# HshMain_v1_1.net
KiCad netlist of a schematic drawn in EAGLE
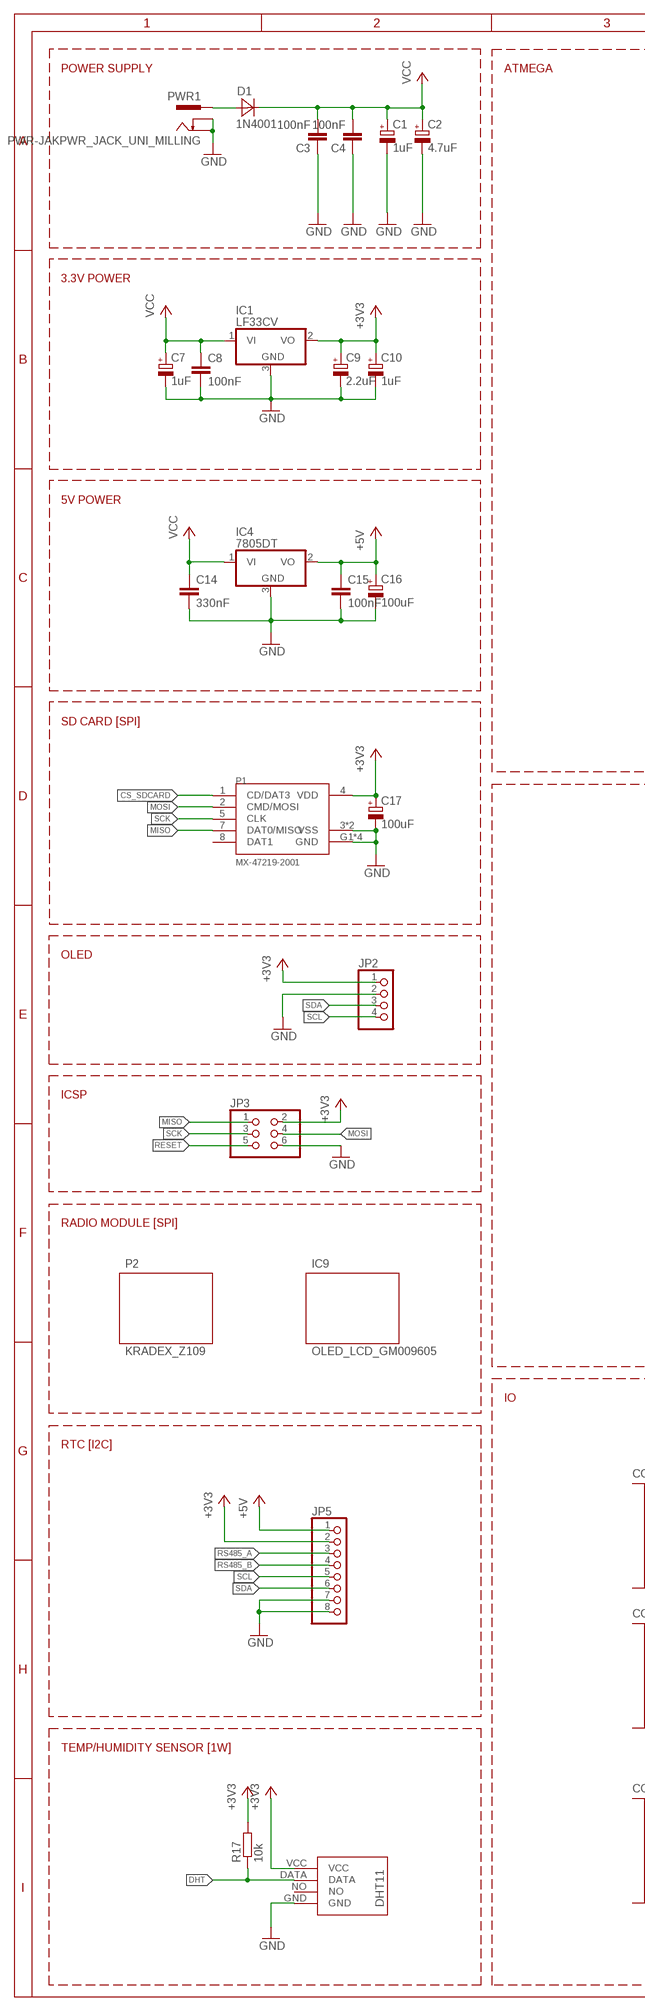
[diagram p0: schematic, sheet 1, part 1 of 2]
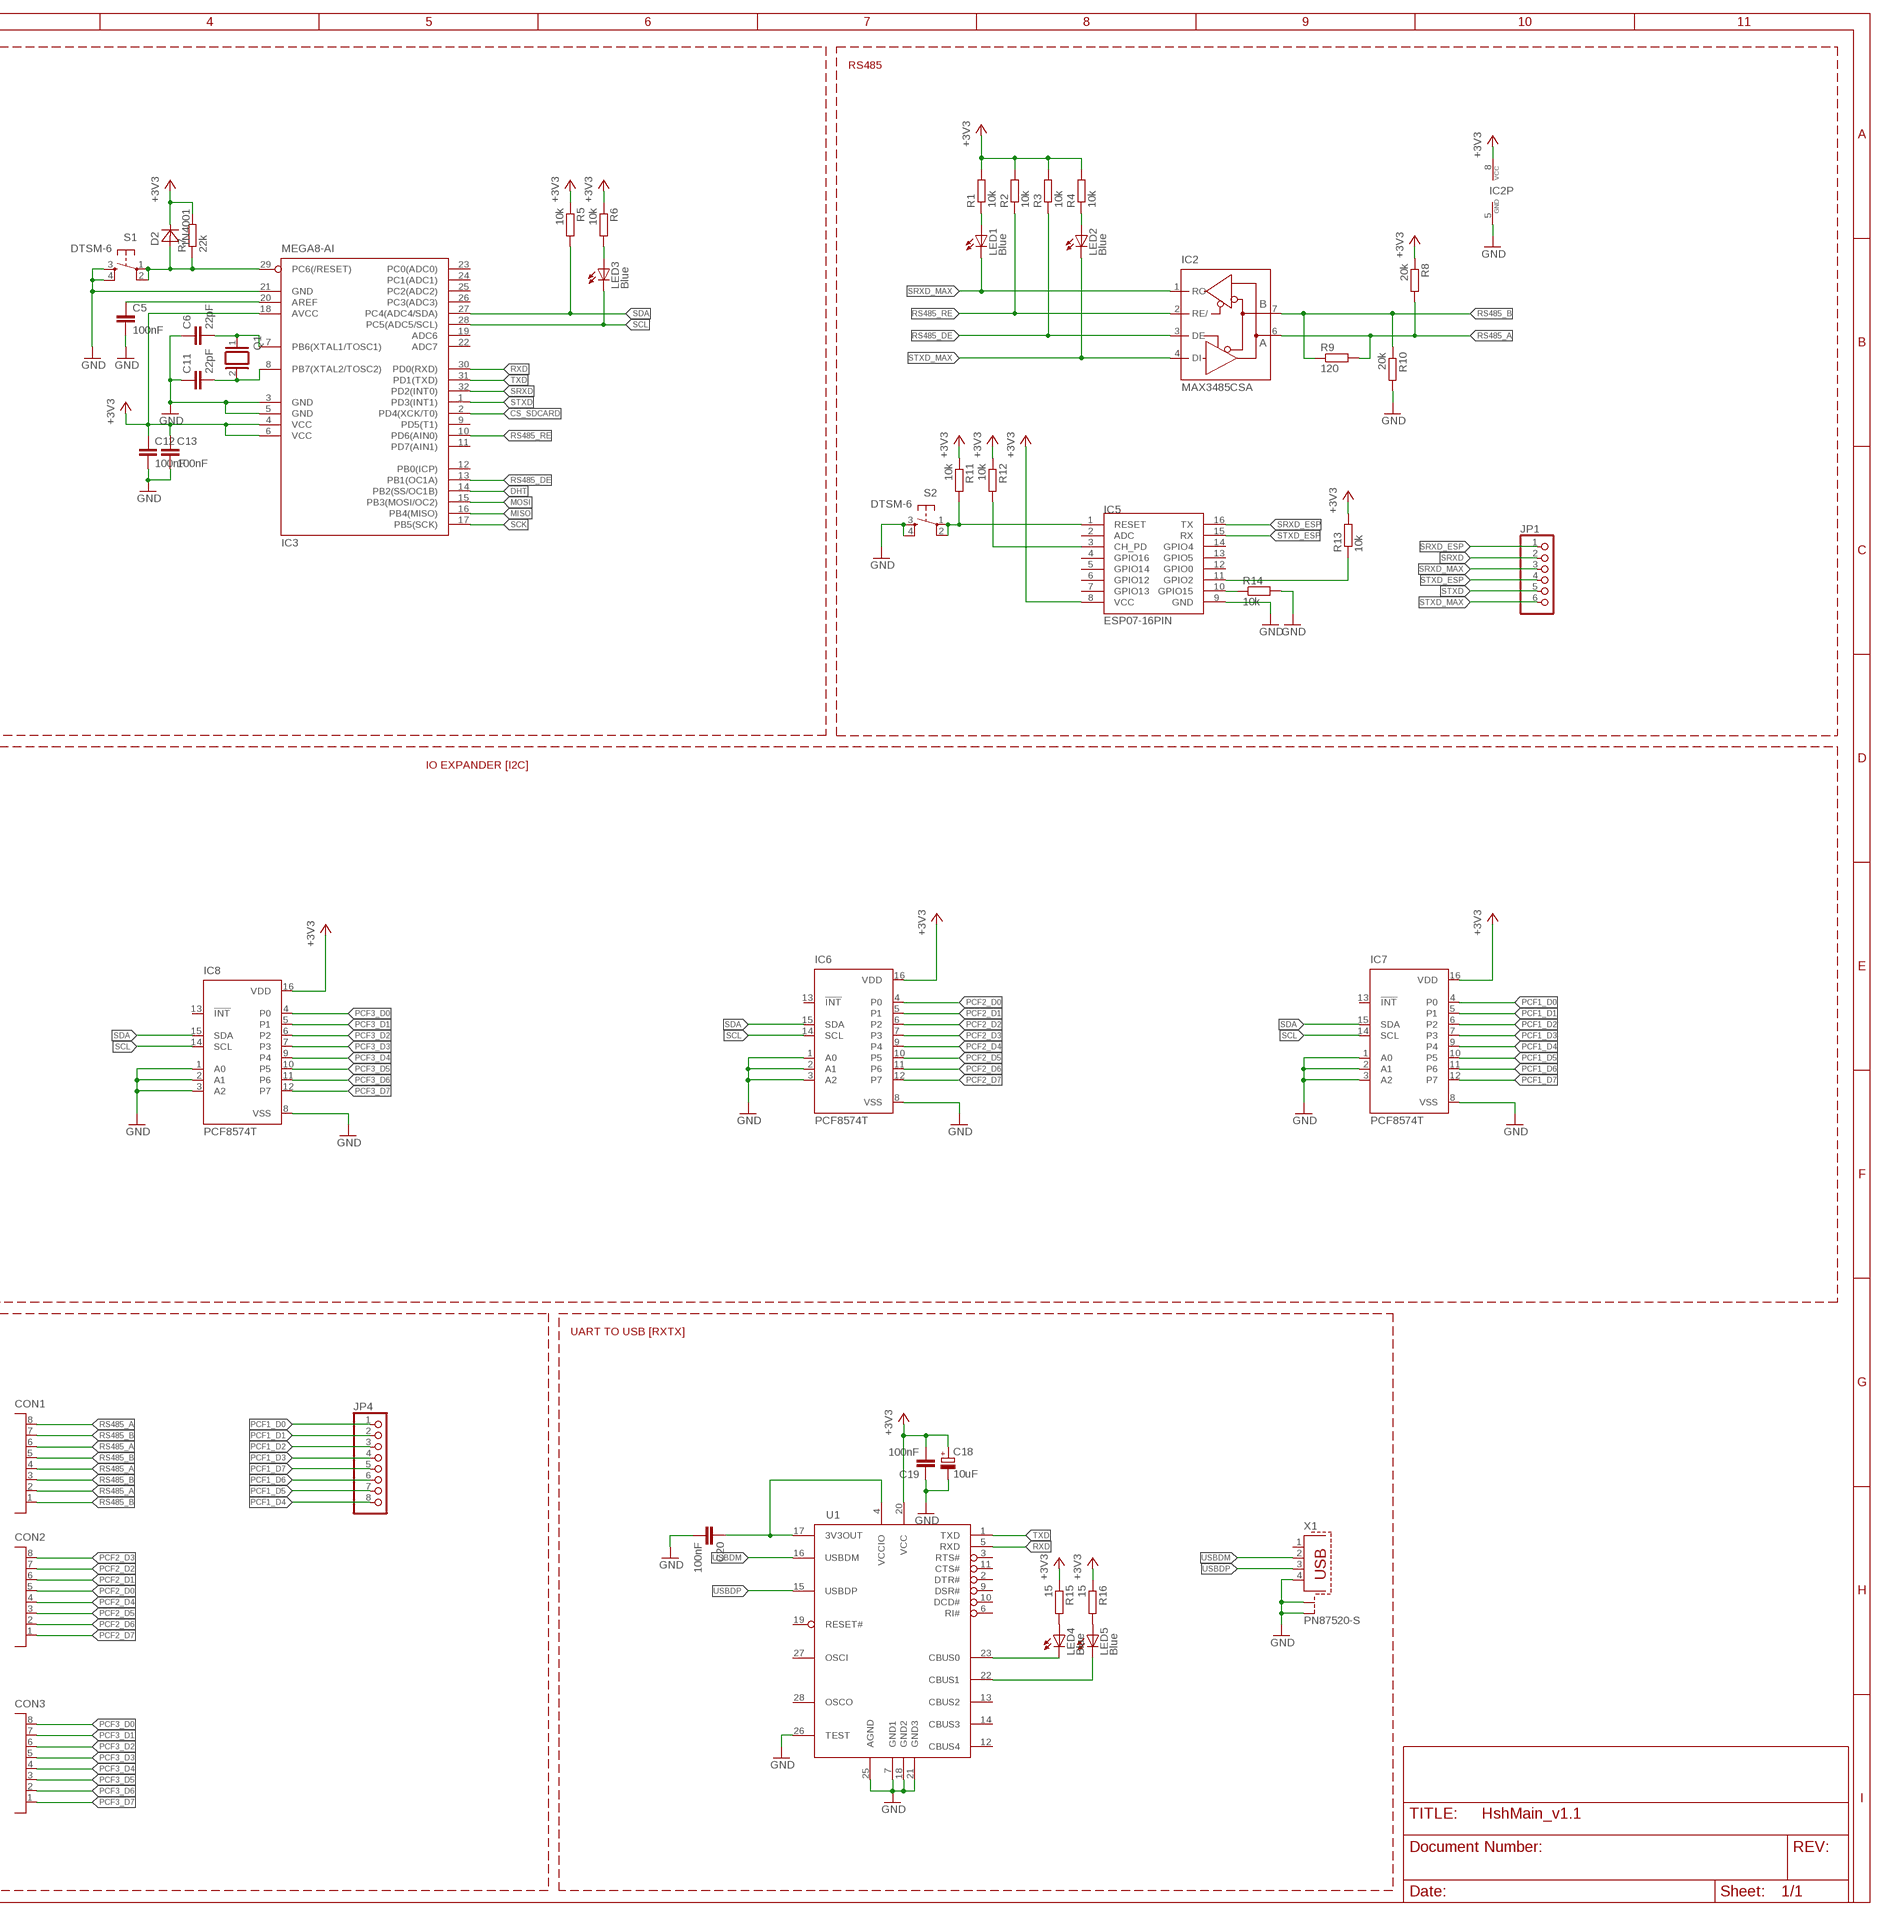
[diagram p1: schematic, sheet 1, part 2 of 2]

(export (version "E")
  (design (tool "Eeschema 10.0.6"))
  (components
    (comp (ref "C1")
      (value "1uF")
      (footprint "eagle-import:PANASONIC_B")
      (libsource (lib "eagle-import") (part "CPOL-EUB"))
    )
    (comp (ref "C2")
      (value "4.7uF")
      (footprint "eagle-import:PANASONIC_B")
      (libsource (lib "eagle-import") (part "CPOL-EUB"))
    )
    (comp (ref "C3")
      (value "100nF")
      (footprint "eagle-import:C0805")
      (libsource (lib "eagle-import") (part "C-EUC0805"))
    )
    (comp (ref "C4")
      (value "100nF")
      (footprint "eagle-import:C0805")
      (libsource (lib "eagle-import") (part "C-EUC0805"))
    )
    (comp (ref "C5")
      (value "100nF")
      (footprint "eagle-import:C0805")
      (libsource (lib "eagle-import") (part "C-EUC0805"))
    )
    (comp (ref "C6")
      (value "22pF")
      (footprint "eagle-import:C0805")
      (libsource (lib "eagle-import") (part "C-EUC0805"))
    )
    (comp (ref "C7")
      (value "1uF")
      (footprint "eagle-import:PANASONIC_B")
      (libsource (lib "eagle-import") (part "CPOL-EUB"))
    )
    (comp (ref "C8")
      (value "100nF")
      (footprint "eagle-import:C0805")
      (libsource (lib "eagle-import") (part "C-EUC0805"))
    )
    (comp (ref "C9")
      (value "2.2uF")
      (footprint "eagle-import:PANASONIC_B")
      (libsource (lib "eagle-import") (part "CPOL-EUB"))
    )
    (comp (ref "C10")
      (value "1uF")
      (footprint "eagle-import:PANASONIC_B")
      (libsource (lib "eagle-import") (part "CPOL-EUB"))
    )
    (comp (ref "C11")
      (value "22pF")
      (footprint "eagle-import:C0805")
      (libsource (lib "eagle-import") (part "C-EUC0805"))
    )
    (comp (ref "C12")
      (value "100nF")
      (footprint "eagle-import:C0805")
      (libsource (lib "eagle-import") (part "C-EUC0805"))
    )
    (comp (ref "C13")
      (value "100nF")
      (footprint "eagle-import:C0805")
      (libsource (lib "eagle-import") (part "C-EUC0805"))
    )
    (comp (ref "C14")
      (value "330nF")
      (footprint "eagle-import:C0805")
      (libsource (lib "eagle-import") (part "C-EUC0805"))
    )
    (comp (ref "C15")
      (value "100nF")
      (footprint "eagle-import:C0805")
      (libsource (lib "eagle-import") (part "C-EUC0805"))
    )
    (comp (ref "C16")
      (value "100uF")
      (footprint "eagle-import:PANASONIC_D")
      (libsource (lib "eagle-import") (part "CPOL-EUD"))
    )
    (comp (ref "C17")
      (value "100uF")
      (footprint "eagle-import:PANASONIC_D")
      (libsource (lib "eagle-import") (part "CPOL-EUD"))
    )
    (comp (ref "C18")
      (value "10uF")
      (footprint "eagle-import:PANASONIC_B")
      (libsource (lib "eagle-import") (part "CPOL-EUB"))
    )
    (comp (ref "C19")
      (value "100nF")
      (footprint "eagle-import:C0805")
      (libsource (lib "eagle-import") (part "C-EUC0805"))
    )
    (comp (ref "C20")
      (value "100nF")
      (footprint "eagle-import:C0805")
      (libsource (lib "eagle-import") (part "C-EUC0805"))
    )
    (comp (ref "CON1")
      (value "15EDGRC-3.81-8P")
      (footprint "eagle-import:15EDGRC-3.81-8P")
      (libsource (lib "eagle-import") (part "15EDGRC-3.81-8P"))
    )
    (comp (ref "CON2")
      (value "15EDGRC-3.81-8P")
      (footprint "eagle-import:15EDGRC-3.81-8P")
      (libsource (lib "eagle-import") (part "15EDGRC-3.81-8P"))
    )
    (comp (ref "CON3")
      (value "15EDGRC-3.81-8P")
      (footprint "eagle-import:15EDGRC-3.81-8P")
      (libsource (lib "eagle-import") (part "15EDGRC-3.81-8P"))
    )
    (comp (ref "D1")
      (value "1N4001")
      (footprint "eagle-import:SMA")
      (libsource (lib "eagle-import") (part "MBRA340T3"))
    )
    (comp (ref "D2")
      (value "1N4001")
      (footprint "eagle-import:SMA")
      (libsource (lib "eagle-import") (part "MBRA340T3"))
    )
    (comp (ref "IC1")
      (value "LF33CV")
      (footprint "eagle-import:TO252")
      (libsource (lib "eagle-import") (part "78DT"))
    )
    (comp (ref "IC2")
      (value "MAX3485CSA")
      (footprint "eagle-import:SO08")
      (fields (field (name "MF") "MAXIM") (field (name "MPN") "MAX481CSA"))
      (libsource (lib "eagle-import") (part "MAX481CSA"))
    )
    (comp (ref "IC3")
      (value "MEGA8-AI")
      (footprint "eagle-import:TQFP32-08")
      (fields (field (name "MPN") "ATMEGA8-16AU"))
      (libsource (lib "eagle-import") (part "MEGA8-AI"))
    )
    (comp (ref "IC4")
      (value "7805DT")
      (footprint "eagle-import:TO252")
      (libsource (lib "eagle-import") (part "linear_78DT05"))
    )
    (comp (ref "IC5")
      (value "ESP07-16PIN")
      (footprint "eagle-import:ESP07-16PIN")
      (libsource (lib "eagle-import") (part "ESP07-16PIN"))
    )
    (comp (ref "IC6")
      (value "PCF8574T")
      (footprint "eagle-import:SO16W")
      (fields (field (name "MPN") "PCF8574T/3,512"))
      (libsource (lib "eagle-import") (part "PCF8574T"))
    )
    (comp (ref "IC7")
      (value "PCF8574T")
      (footprint "eagle-import:SO16W")
      (fields (field (name "MPN") "PCF8574T/3,512"))
      (libsource (lib "eagle-import") (part "PCF8574T"))
    )
    (comp (ref "IC8")
      (value "PCF8574T")
      (footprint "eagle-import:SO16W")
      (fields (field (name "MPN") "PCF8574T/3,512"))
      (libsource (lib "eagle-import") (part "PCF8574T"))
    )
    (comp (ref "IC9")
      (value "OLED_LCD_GM009605")
      (footprint "eagle-import:OLED_LCD_GM009605")
      (libsource (lib "eagle-import") (part "OLED_LCD_GM009605"))
    )
    (comp (ref "IC10")
      (value "DHT11-PION.")
      (footprint "eagle-import:DHT11-PION.")
      (libsource (lib "eagle-import") (part "DHT11-PION."))
    )
    (comp (ref "JP1")
      (value "PINHD-1X6")
      (footprint "eagle-import:1X06")
      (libsource (lib "eagle-import") (part "PINHD-1X6"))
    )
    (comp (ref "JP2")
      (value "PINHD-1X4")
      (footprint "eagle-import:1X04")
      (libsource (lib "eagle-import") (part "PINHD-1X4"))
    )
    (comp (ref "JP3")
      (value "PINHD-2X3")
      (footprint "eagle-import:2X03")
      (libsource (lib "eagle-import") (part "PINHD-2X3"))
    )
    (comp (ref "JP4")
      (value "PINHD-1X8")
      (footprint "eagle-import:1X08")
      (libsource (lib "eagle-import") (part "PINHD-1X8"))
    )
    (comp (ref "JP5")
      (value "PINHD-1X8/90")
      (footprint "eagle-import:1X08_90")
      (libsource (lib "eagle-import") (part "PINHD-1X8/90"))
    )
    (comp (ref "LED1")
      (value "Blue")
      (footprint "eagle-import:SML0805")
      (libsource (lib "eagle-import") (part "LEDSML0805"))
    )
    (comp (ref "LED2")
      (value "Blue")
      (footprint "eagle-import:SML0805")
      (libsource (lib "eagle-import") (part "LEDSML0805"))
    )
    (comp (ref "LED3")
      (value "Blue")
      (footprint "eagle-import:SML0805")
      (libsource (lib "eagle-import") (part "LEDSML0805"))
    )
    (comp (ref "LED4")
      (value "Blue")
      (footprint "eagle-import:SML0805")
      (libsource (lib "eagle-import") (part "LEDSML0805"))
    )
    (comp (ref "LED5")
      (value "Blue")
      (footprint "eagle-import:SML0805")
      (libsource (lib "eagle-import") (part "LEDSML0805"))
    )
    (comp (ref "P1")
      (value "MX-47219-2001")
      (footprint "eagle-import:MX-47219-2001")
      (libsource (lib "eagle-import") (part "MX-47219-2001"))
    )
    (comp (ref "P2")
      (value "KRADEX_Z109")
      (footprint "eagle-import:KRADEX_Z109")
      (libsource (lib "eagle-import") (part "KRADEX_Z109"))
    )
    (comp (ref "PWR1")
      (value "PWR-JAKPWR_JACK_UNI_MILLING")
      (footprint "eagle-import:PWR_JACK_UNI_MILLING")
      (libsource (lib "eagle-import") (part "PWR-JAKPWR_JACK_UNI_MILLING"))
    )
    (comp (ref "Q1")
      (value "XTAL/S")
      (footprint "eagle-import:QS")
      (libsource (lib "eagle-import") (part "XTAL/S"))
    )
    (comp (ref "R1")
      (value "10k")
      (footprint "eagle-import:R0805")
      (libsource (lib "eagle-import") (part "R-EU_R0805"))
    )
    (comp (ref "R2")
      (value "10k")
      (footprint "eagle-import:R0805")
      (libsource (lib "eagle-import") (part "R-EU_R0805"))
    )
    (comp (ref "R3")
      (value "10k")
      (footprint "eagle-import:R0805")
      (libsource (lib "eagle-import") (part "R-EU_R0805"))
    )
    (comp (ref "R4")
      (value "10k")
      (footprint "eagle-import:R0805")
      (libsource (lib "eagle-import") (part "R-EU_R0805"))
    )
    (comp (ref "R5")
      (value "10k")
      (footprint "eagle-import:R0805")
      (libsource (lib "eagle-import") (part "R-EU_R0805"))
    )
    (comp (ref "R6")
      (value "10k")
      (footprint "eagle-import:R0805")
      (libsource (lib "eagle-import") (part "R-EU_R0805"))
    )
    (comp (ref "R7")
      (value "22k")
      (footprint "eagle-import:R0805")
      (libsource (lib "eagle-import") (part "R-EU_R0805"))
    )
    (comp (ref "R8")
      (value "20k")
      (footprint "eagle-import:R0805")
      (libsource (lib "eagle-import") (part "R-EU_R0805"))
    )
    (comp (ref "R9")
      (value "120")
      (footprint "eagle-import:R0805")
      (libsource (lib "eagle-import") (part "R-EU_R0805"))
    )
    (comp (ref "R10")
      (value "20k")
      (footprint "eagle-import:R0805")
      (libsource (lib "eagle-import") (part "R-EU_R0805"))
    )
    (comp (ref "R11")
      (value "10k")
      (footprint "eagle-import:R0805")
      (libsource (lib "eagle-import") (part "R-EU_R0805"))
    )
    (comp (ref "R12")
      (value "10k")
      (footprint "eagle-import:R0805")
      (libsource (lib "eagle-import") (part "R-EU_R0805"))
    )
    (comp (ref "R13")
      (value "10k")
      (footprint "eagle-import:R0805")
      (libsource (lib "eagle-import") (part "R-EU_R0805"))
    )
    (comp (ref "R14")
      (value "10k")
      (footprint "eagle-import:R0805")
      (libsource (lib "eagle-import") (part "R-EU_R0805"))
    )
    (comp (ref "R15")
      (value "15")
      (footprint "eagle-import:R0805")
      (libsource (lib "eagle-import") (part "R-EU_R0805"))
    )
    (comp (ref "R16")
      (value "15")
      (footprint "eagle-import:R0805")
      (libsource (lib "eagle-import") (part "R-EU_R0805"))
    )
    (comp (ref "R17")
      (value "10k")
      (footprint "eagle-import:R0805")
      (libsource (lib "eagle-import") (part "R-EU_R0805"))
    )
    (comp (ref "S1")
      (value "DTSM-6")
      (footprint "eagle-import:DTSM-6")
      (libsource (lib "eagle-import") (part "DTSM-6"))
    )
    (comp (ref "S2")
      (value "DTSM-6")
      (footprint "eagle-import:DTSM-6")
      (libsource (lib "eagle-import") (part "DTSM-6"))
    )
    (comp (ref "U1")
      (value "FT232RL")
      (footprint "eagle-import:SSOP28DB")
      (libsource (lib "eagle-import") (part "FT232RL"))
    )
    (comp (ref "X1")
      (value "PN87520-S")
      (footprint "eagle-import:PN87520-S")
      (libsource (lib "eagle-import") (part "PN87520-S"))
    )
  )
  (nets
    (net (code "1") (name "+3V3") (class "Default")
      (node (ref "C10") (pin "+") (pinfunction "+_+") (pintype "passive"))
      (node (ref "C12") (pin "1") (pinfunction "1_1") (pintype "passive"))
      (node (ref "C13") (pin "1") (pinfunction "1_1") (pintype "passive"))
      (node (ref "C17") (pin "+") (pinfunction "+_+") (pintype "passive"))
      (node (ref "C18") (pin "+") (pinfunction "+_+") (pintype "passive"))
      (node (ref "C19") (pin "2") (pinfunction "2_2") (pintype "passive"))
      (node (ref "C9") (pin "+") (pinfunction "+_+") (pintype "passive"))
      (node (ref "D2") (pin "C") (pinfunction "C_C") (pintype "passive"))
      (node (ref "IC1") (pin "2") (pinfunction "VO_2") (pintype "passive"))
      (node (ref "IC10") (pin "VCC") (pinfunction "VCC_VCC") (pintype "bidirectional"))
      (node (ref "IC2") (pin "8") (pinfunction "VCC_8") (pintype "power_in"))
      (node (ref "IC3") (pin "18") (pinfunction "AVCC_18") (pintype "power_in"))
      (node (ref "IC3") (pin "4") (pinfunction "VCC_4") (pintype "power_in"))
      (node (ref "IC3") (pin "6") (pinfunction "VCC_6") (pintype "power_in"))
      (node (ref "IC5") (pin "8") (pinfunction "VCC_8") (pintype "bidirectional"))
      (node (ref "IC6") (pin "16") (pinfunction "VDD_16") (pintype "power_in"))
      (node (ref "IC7") (pin "16") (pinfunction "VDD_16") (pintype "power_in"))
      (node (ref "IC8") (pin "16") (pinfunction "VDD_16") (pintype "power_in"))
      (node (ref "JP2") (pin "1") (pinfunction "1_1") (pintype "passive"))
      (node (ref "JP3") (pin "2") (pinfunction "2_2") (pintype "passive"))
      (node (ref "JP5") (pin "2") (pinfunction "2_2") (pintype "passive"))
      (node (ref "P1") (pin "4") (pinfunction "VDD_4") (pintype "bidirectional"))
      (node (ref "R1") (pin "2") (pinfunction "2_2") (pintype "passive"))
      (node (ref "R11") (pin "1") (pinfunction "1_1") (pintype "passive"))
      (node (ref "R12") (pin "1") (pinfunction "1_1") (pintype "passive"))
      (node (ref "R13") (pin "2") (pinfunction "2_2") (pintype "passive"))
      (node (ref "R15") (pin "1") (pinfunction "1_1") (pintype "passive"))
      (node (ref "R16") (pin "1") (pinfunction "1_1") (pintype "passive"))
      (node (ref "R17") (pin "2") (pinfunction "2_2") (pintype "passive"))
      (node (ref "R2") (pin "2") (pinfunction "2_2") (pintype "passive"))
      (node (ref "R3") (pin "2") (pinfunction "2_2") (pintype "passive"))
      (node (ref "R4") (pin "2") (pinfunction "2_2") (pintype "passive"))
      (node (ref "R5") (pin "1") (pinfunction "1_1") (pintype "passive"))
      (node (ref "R6") (pin "1") (pinfunction "1_1") (pintype "passive"))
      (node (ref "R7") (pin "2") (pinfunction "2_2") (pintype "passive"))
      (node (ref "R8") (pin "1") (pinfunction "1_1") (pintype "passive"))
      (node (ref "U1") (pin "20") (pinfunction "VCC_20") (pintype "power_in"))
    )
    (net (code "2") (name "+5V") (class "Default")
      (node (ref "C15") (pin "1") (pinfunction "1_1") (pintype "passive"))
      (node (ref "C16") (pin "+") (pinfunction "+_+") (pintype "passive"))
      (node (ref "IC4") (pin "2") (pinfunction "VO_2") (pintype "passive"))
      (node (ref "JP5") (pin "1") (pinfunction "1_1") (pintype "passive"))
    )
    (net (code "3") (name "CS_SDCARD") (class "Default")
      (node (ref "IC3") (pin "2") (pinfunction "PD4(XCK/T0)_2") (pintype "bidirectional"))
      (node (ref "P1") (pin "1") (pinfunction "CD/DAT3_1") (pintype "bidirectional"))
    )
    (net (code "4") (name "DHT") (class "Default")
      (node (ref "IC10") (pin "DATA") (pinfunction "DATA_DATA") (pintype "bidirectional"))
      (node (ref "IC3") (pin "14") (pinfunction "PB2(SS/OC1B)_14") (pintype "bidirectional"))
      (node (ref "R17") (pin "1") (pinfunction "1_1") (pintype "passive"))
    )
    (net (code "5") (name "GND") (class "Default")
      (node (ref "C1") (pin "-") (pinfunction "-_-") (pintype "passive"))
      (node (ref "C10") (pin "-") (pinfunction "-_-") (pintype "passive"))
      (node (ref "C11") (pin "1") (pinfunction "1_1") (pintype "passive"))
      (node (ref "C12") (pin "2") (pinfunction "2_2") (pintype "passive"))
      (node (ref "C13") (pin "2") (pinfunction "2_2") (pintype "passive"))
      (node (ref "C14") (pin "2") (pinfunction "2_2") (pintype "passive"))
      (node (ref "C15") (pin "2") (pinfunction "2_2") (pintype "passive"))
      (node (ref "C16") (pin "-") (pinfunction "-_-") (pintype "passive"))
      (node (ref "C17") (pin "-") (pinfunction "-_-") (pintype "passive"))
      (node (ref "C18") (pin "-") (pinfunction "-_-") (pintype "passive"))
      (node (ref "C19") (pin "1") (pinfunction "1_1") (pintype "passive"))
      (node (ref "C2") (pin "-") (pinfunction "-_-") (pintype "passive"))
      (node (ref "C20") (pin "2") (pinfunction "2_2") (pintype "passive"))
      (node (ref "C3") (pin "1") (pinfunction "1_1") (pintype "passive"))
      (node (ref "C4") (pin "1") (pinfunction "1_1") (pintype "passive"))
      (node (ref "C5") (pin "2") (pinfunction "2_2") (pintype "passive"))
      (node (ref "C6") (pin "1") (pinfunction "1_1") (pintype "passive"))
      (node (ref "C7") (pin "-") (pinfunction "-_-") (pintype "passive"))
      (node (ref "C8") (pin "2") (pinfunction "2_2") (pintype "passive"))
      (node (ref "C9") (pin "-") (pinfunction "-_-") (pintype "passive"))
      (node (ref "IC1") (pin "3") (pinfunction "GND_3") (pintype "passive"))
      (node (ref "IC10") (pin "GND") (pinfunction "GND_GND") (pintype "bidirectional"))
      (node (ref "IC2") (pin "5") (pinfunction "GND_5") (pintype "power_in"))
      (node (ref "IC3") (pin "21") (pinfunction "GND_21") (pintype "power_in"))
      (node (ref "IC3") (pin "3") (pinfunction "GND_3") (pintype "power_in"))
      (node (ref "IC3") (pin "5") (pinfunction "GND_5") (pintype "power_in"))
      (node (ref "IC4") (pin "3") (pinfunction "GND_3") (pintype "passive"))
      (node (ref "IC5") (pin "9") (pinfunction "GND_9") (pintype "bidirectional"))
      (node (ref "IC6") (pin "1") (pinfunction "A0_1") (pintype "input"))
      (node (ref "IC6") (pin "2") (pinfunction "A1_2") (pintype "input"))
      (node (ref "IC6") (pin "3") (pinfunction "A2_3") (pintype "input"))
      (node (ref "IC6") (pin "8") (pinfunction "VSS_8") (pintype "power_in"))
      (node (ref "IC7") (pin "1") (pinfunction "A0_1") (pintype "input"))
      (node (ref "IC7") (pin "2") (pinfunction "A1_2") (pintype "input"))
      (node (ref "IC7") (pin "3") (pinfunction "A2_3") (pintype "input"))
      (node (ref "IC7") (pin "8") (pinfunction "VSS_8") (pintype "power_in"))
      (node (ref "IC8") (pin "1") (pinfunction "A0_1") (pintype "input"))
      (node (ref "IC8") (pin "2") (pinfunction "A1_2") (pintype "input"))
      (node (ref "IC8") (pin "3") (pinfunction "A2_3") (pintype "input"))
      (node (ref "IC8") (pin "8") (pinfunction "VSS_8") (pintype "power_in"))
      (node (ref "JP2") (pin "2") (pinfunction "2_2") (pintype "passive"))
      (node (ref "JP3") (pin "6") (pinfunction "6_6") (pintype "passive"))
      (node (ref "JP5") (pin "7") (pinfunction "7_7") (pintype "passive"))
      (node (ref "JP5") (pin "8") (pinfunction "8_8") (pintype "passive"))
      (node (ref "P1") (pin "3") (pinfunction "VSS_3") (pintype "bidirectional"))
      (node (ref "P1") (pin "6") (pinfunction "VSS_6") (pintype "bidirectional"))
      (node (ref "P1") (pin "G1") (pinfunction "GND_G1") (pintype "bidirectional"))
      (node (ref "P1") (pin "G2") (pinfunction "GND_G2") (pintype "bidirectional"))
      (node (ref "P1") (pin "G3") (pinfunction "GND_G3") (pintype "bidirectional"))
      (node (ref "P1") (pin "G4") (pinfunction "GND_G4") (pintype "bidirectional"))
      (node (ref "PWR1") (pin "-") (pinfunction "-_-") (pintype "passive"))
      (node (ref "PWR1") (pin "--") (pinfunction "--_--") (pintype "passive"))
      (node (ref "PWR1") (pin "--1") (pinfunction "--_--1") (pintype "passive"))
      (node (ref "PWR1") (pin "--2") (pinfunction "--_--2") (pintype "passive"))
      (node (ref "PWR1") (pin "--3") (pinfunction "--_--3") (pintype "passive"))
      (node (ref "PWR1") (pin "--4") (pinfunction "--_--4") (pintype "passive"))
      (node (ref "PWR1") (pin "--5") (pinfunction "--_--5") (pintype "passive"))
      (node (ref "PWR1") (pin "--6") (pinfunction "--_--6") (pintype "passive"))
      (node (ref "PWR1") (pin "--7") (pinfunction "--_--7") (pintype "passive"))
      (node (ref "PWR1") (pin "--8") (pinfunction "--_--8") (pintype "passive"))
      (node (ref "PWR1") (pin "-1") (pinfunction "-_-1") (pintype "passive"))
      (node (ref "PWR1") (pin "-2") (pinfunction "-_-2") (pintype "passive"))
      (node (ref "PWR1") (pin "-3") (pinfunction "-_-3") (pintype "passive"))
      (node (ref "PWR1") (pin "-4") (pinfunction "-_-4") (pintype "passive"))
      (node (ref "PWR1") (pin "-5") (pinfunction "-_-5") (pintype "passive"))
      (node (ref "PWR1") (pin "-6") (pinfunction "-_-6") (pintype "passive"))
      (node (ref "PWR1") (pin "-7") (pinfunction "-_-7") (pintype "passive"))
      (node (ref "PWR1") (pin "-8") (pinfunction "-_-8") (pintype "passive"))
      (node (ref "R10") (pin "2") (pinfunction "2_2") (pintype "passive"))
      (node (ref "R14") (pin "2") (pinfunction "2_2") (pintype "passive"))
      (node (ref "S1") (pin "3") (pinfunction "3_3") (pintype "passive"))
      (node (ref "S1") (pin "4") (pinfunction "4_4") (pintype "passive"))
      (node (ref "S2") (pin "3") (pinfunction "3_3") (pintype "passive"))
      (node (ref "S2") (pin "4") (pinfunction "4_4") (pintype "passive"))
      (node (ref "U1") (pin "18") (pinfunction "GND2_18") (pintype "power_in"))
      (node (ref "U1") (pin "21") (pinfunction "GND3_21") (pintype "power_in"))
      (node (ref "U1") (pin "25") (pinfunction "AGND_25") (pintype "power_in"))
      (node (ref "U1") (pin "26") (pinfunction "TEST_26") (pintype "input"))
      (node (ref "U1") (pin "7") (pinfunction "GND1_7") (pintype "power_in"))
      (node (ref "X1") (pin "4") (pinfunction "4_4") (pintype "passive"))
      (node (ref "X1") (pin "S1") (pinfunction "S1_S1") (pintype "passive"))
      (node (ref "X1") (pin "S2") (pinfunction "S2_S2") (pintype "passive"))
    )
    (net (code "6") (name "MISO") (class "Default")
      (node (ref "IC3") (pin "16") (pinfunction "PB4(MISO)_16") (pintype "bidirectional"))
      (node (ref "JP3") (pin "1") (pinfunction "1_1") (pintype "passive"))
      (node (ref "P1") (pin "7") (pinfunction "DAT0/MISO_7") (pintype "bidirectional"))
    )
    (net (code "7") (name "MOSI") (class "Default")
      (node (ref "IC3") (pin "15") (pinfunction "PB3(MOSI/OC2)_15") (pintype "bidirectional"))
      (node (ref "JP3") (pin "4") (pinfunction "4_4") (pintype "passive"))
      (node (ref "P1") (pin "2") (pinfunction "CMD/MOSI_2") (pintype "bidirectional"))
    )
    (net (code "8") (name "Net-(D1-PadA)") (class "Default")
      (node (ref "D1") (pin "A") (pinfunction "A_A") (pintype "passive"))
      (node (ref "PWR1") (pin "+") (pinfunction "+_+") (pintype "passive"))
      (node (ref "PWR1") (pin "+1") (pinfunction "+_+1") (pintype "passive"))
      (node (ref "PWR1") (pin "+2") (pinfunction "+_+2") (pintype "passive"))
      (node (ref "PWR1") (pin "+3") (pinfunction "+_+3") (pintype "passive"))
      (node (ref "PWR1") (pin "+4") (pinfunction "+_+4") (pintype "passive"))
      (node (ref "PWR1") (pin "+5") (pinfunction "+_+5") (pintype "passive"))
      (node (ref "PWR1") (pin "+6") (pinfunction "+_+6") (pintype "passive"))
      (node (ref "PWR1") (pin "+7") (pinfunction "+_+7") (pintype "passive"))
      (node (ref "PWR1") (pin "+8") (pinfunction "+_+8") (pintype "passive"))
    )
    (net (code "9") (name "Net-(IC3-AREF)") (class "Default")
      (node (ref "C5") (pin "1") (pinfunction "1_1") (pintype "passive"))
      (node (ref "IC3") (pin "20") (pinfunction "AREF_20") (pintype "passive"))
    )
    (net (code "10") (name "Net-(IC3-PB6(XTAL1{slash}TOSC1))") (class "Default")
      (node (ref "C6") (pin "2") (pinfunction "2_2") (pintype "passive"))
      (node (ref "IC3") (pin "7") (pinfunction "PB6(XTAL1/TOSC1)_7") (pintype "bidirectional"))
      (node (ref "Q1") (pin "1") (pinfunction "1_1") (pintype "passive"))
    )
    (net (code "11") (name "Net-(IC3-PB7(XTAL2{slash}TOSC2))") (class "Default")
      (node (ref "C11") (pin "2") (pinfunction "2_2") (pintype "passive"))
      (node (ref "IC3") (pin "8") (pinfunction "PB7(XTAL2/TOSC2)_8") (pintype "bidirectional"))
      (node (ref "Q1") (pin "2") (pinfunction "2_2") (pintype "passive"))
    )
    (net (code "12") (name "Net-(IC5-CH_PD)") (class "Default")
      (node (ref "IC5") (pin "3") (pinfunction "CH_PD_3") (pintype "bidirectional"))
      (node (ref "R12") (pin "2") (pinfunction "2_2") (pintype "passive"))
    )
    (net (code "13") (name "Net-(IC5-GPIO2)") (class "Default")
      (node (ref "IC5") (pin "11") (pinfunction "GPIO2_11") (pintype "bidirectional"))
      (node (ref "R13") (pin "1") (pinfunction "1_1") (pintype "passive"))
    )
    (net (code "14") (name "Net-(IC5-GPIO15)") (class "Default")
      (node (ref "IC5") (pin "10") (pinfunction "GPIO15_10") (pintype "bidirectional"))
      (node (ref "R14") (pin "1") (pinfunction "1_1") (pintype "passive"))
    )
    (net (code "15") (name "Net-(IC5-RESET)") (class "Default")
      (node (ref "IC5") (pin "1") (pinfunction "RESET_1") (pintype "bidirectional"))
      (node (ref "R11") (pin "2") (pinfunction "2_2") (pintype "passive"))
      (node (ref "S2") (pin "1") (pinfunction "1_1") (pintype "passive"))
      (node (ref "S2") (pin "2") (pinfunction "2_2") (pintype "passive"))
    )
    (net (code "16") (name "Net-(LED1-PadA)") (class "Default")
      (node (ref "LED1") (pin "A") (pinfunction "A_A") (pintype "passive"))
      (node (ref "R1") (pin "1") (pinfunction "1_1") (pintype "passive"))
    )
    (net (code "17") (name "Net-(LED2-PadA)") (class "Default")
      (node (ref "LED2") (pin "A") (pinfunction "A_A") (pintype "passive"))
      (node (ref "R4") (pin "1") (pinfunction "1_1") (pintype "passive"))
    )
    (net (code "18") (name "Net-(LED3-PadA)") (class "Default")
      (node (ref "LED3") (pin "A") (pinfunction "A_A") (pintype "passive"))
      (node (ref "R6") (pin "2") (pinfunction "2_2") (pintype "passive"))
    )
    (net (code "19") (name "Net-(LED4-PadA)") (class "Default")
      (node (ref "LED4") (pin "A") (pinfunction "A_A") (pintype "passive"))
      (node (ref "R15") (pin "2") (pinfunction "2_2") (pintype "passive"))
    )
    (net (code "20") (name "Net-(LED5-PadA)") (class "Default")
      (node (ref "LED5") (pin "A") (pinfunction "A_A") (pintype "passive"))
      (node (ref "R16") (pin "2") (pinfunction "2_2") (pintype "passive"))
    )
    (net (code "21") (name "Net-(U1-3V3OUT)") (class "Default")
      (node (ref "C20") (pin "1") (pinfunction "1_1") (pintype "passive"))
      (node (ref "U1") (pin "17") (pinfunction "3V3OUT_17") (pintype "output"))
      (node (ref "U1") (pin "4") (pinfunction "VCCIO_4") (pintype "power_in"))
    )
    (net (code "22") (name "Net-(U1-CBUS0)") (class "Default")
      (node (ref "LED4") (pin "C") (pinfunction "C_C") (pintype "passive"))
      (node (ref "U1") (pin "23") (pinfunction "CBUS0_23") (pintype "bidirectional"))
    )
    (net (code "23") (name "Net-(U1-CBUS1)") (class "Default")
      (node (ref "LED5") (pin "C") (pinfunction "C_C") (pintype "passive"))
      (node (ref "U1") (pin "22") (pinfunction "CBUS1_22") (pintype "bidirectional"))
    )
    (net (code "24") (name "PCF1_D0") (class "Default")
      (node (ref "IC7") (pin "4") (pinfunction "P0_4") (pintype "bidirectional"))
      (node (ref "JP4") (pin "1") (pinfunction "1_1") (pintype "passive"))
    )
    (net (code "25") (name "PCF1_D1") (class "Default")
      (node (ref "IC7") (pin "5") (pinfunction "P1_5") (pintype "bidirectional"))
      (node (ref "JP4") (pin "2") (pinfunction "2_2") (pintype "passive"))
    )
    (net (code "26") (name "PCF1_D2") (class "Default")
      (node (ref "IC7") (pin "6") (pinfunction "P2_6") (pintype "bidirectional"))
      (node (ref "JP4") (pin "3") (pinfunction "3_3") (pintype "passive"))
    )
    (net (code "27") (name "PCF1_D3") (class "Default")
      (node (ref "IC7") (pin "7") (pinfunction "P3_7") (pintype "bidirectional"))
      (node (ref "JP4") (pin "4") (pinfunction "4_4") (pintype "passive"))
    )
    (net (code "28") (name "PCF1_D4") (class "Default")
      (node (ref "IC7") (pin "9") (pinfunction "P4_9") (pintype "bidirectional"))
      (node (ref "JP4") (pin "8") (pinfunction "8_8") (pintype "passive"))
    )
    (net (code "29") (name "PCF1_D5") (class "Default")
      (node (ref "IC7") (pin "10") (pinfunction "P5_10") (pintype "bidirectional"))
      (node (ref "JP4") (pin "7") (pinfunction "7_7") (pintype "passive"))
    )
    (net (code "30") (name "PCF1_D6") (class "Default")
      (node (ref "IC7") (pin "11") (pinfunction "P6_11") (pintype "bidirectional"))
      (node (ref "JP4") (pin "6") (pinfunction "6_6") (pintype "passive"))
    )
    (net (code "31") (name "PCF1_D7") (class "Default")
      (node (ref "IC7") (pin "12") (pinfunction "P7_12") (pintype "bidirectional"))
      (node (ref "JP4") (pin "5") (pinfunction "5_5") (pintype "passive"))
    )
    (net (code "32") (name "PCF2_D0") (class "Default")
      (node (ref "CON2") (pin "5") (pinfunction "P$5_5") (pintype "bidirectional"))
      (node (ref "IC6") (pin "4") (pinfunction "P0_4") (pintype "bidirectional"))
    )
    (net (code "33") (name "PCF2_D1") (class "Default")
      (node (ref "CON2") (pin "6") (pinfunction "P$6_6") (pintype "bidirectional"))
      (node (ref "IC6") (pin "5") (pinfunction "P1_5") (pintype "bidirectional"))
    )
    (net (code "34") (name "PCF2_D2") (class "Default")
      (node (ref "CON2") (pin "7") (pinfunction "P$7_7") (pintype "bidirectional"))
      (node (ref "IC6") (pin "6") (pinfunction "P2_6") (pintype "bidirectional"))
    )
    (net (code "35") (name "PCF2_D3") (class "Default")
      (node (ref "CON2") (pin "8") (pinfunction "P$8_8") (pintype "bidirectional"))
      (node (ref "IC6") (pin "7") (pinfunction "P3_7") (pintype "bidirectional"))
    )
    (net (code "36") (name "PCF2_D4") (class "Default")
      (node (ref "CON2") (pin "4") (pinfunction "P$4_4") (pintype "bidirectional"))
      (node (ref "IC6") (pin "9") (pinfunction "P4_9") (pintype "bidirectional"))
    )
    (net (code "37") (name "PCF2_D5") (class "Default")
      (node (ref "CON2") (pin "3") (pinfunction "P$3_3") (pintype "bidirectional"))
      (node (ref "IC6") (pin "10") (pinfunction "P5_10") (pintype "bidirectional"))
    )
    (net (code "38") (name "PCF2_D6") (class "Default")
      (node (ref "CON2") (pin "2") (pinfunction "P$2_2") (pintype "bidirectional"))
      (node (ref "IC6") (pin "11") (pinfunction "P6_11") (pintype "bidirectional"))
    )
    (net (code "39") (name "PCF2_D7") (class "Default")
      (node (ref "CON2") (pin "1") (pinfunction "P$1_1") (pintype "bidirectional"))
      (node (ref "IC6") (pin "12") (pinfunction "P7_12") (pintype "bidirectional"))
    )
    (net (code "40") (name "PCF3_D0") (class "Default")
      (node (ref "CON3") (pin "8") (pinfunction "P$8_8") (pintype "bidirectional"))
      (node (ref "IC8") (pin "4") (pinfunction "P0_4") (pintype "bidirectional"))
    )
    (net (code "41") (name "PCF3_D1") (class "Default")
      (node (ref "CON3") (pin "7") (pinfunction "P$7_7") (pintype "bidirectional"))
      (node (ref "IC8") (pin "5") (pinfunction "P1_5") (pintype "bidirectional"))
    )
    (net (code "42") (name "PCF3_D2") (class "Default")
      (node (ref "CON3") (pin "6") (pinfunction "P$6_6") (pintype "bidirectional"))
      (node (ref "IC8") (pin "6") (pinfunction "P2_6") (pintype "bidirectional"))
    )
    (net (code "43") (name "PCF3_D3") (class "Default")
      (node (ref "CON3") (pin "5") (pinfunction "P$5_5") (pintype "bidirectional"))
      (node (ref "IC8") (pin "7") (pinfunction "P3_7") (pintype "bidirectional"))
    )
    (net (code "44") (name "PCF3_D4") (class "Default")
      (node (ref "CON3") (pin "4") (pinfunction "P$4_4") (pintype "bidirectional"))
      (node (ref "IC8") (pin "9") (pinfunction "P4_9") (pintype "bidirectional"))
    )
    (net (code "45") (name "PCF3_D5") (class "Default")
      (node (ref "CON3") (pin "3") (pinfunction "P$3_3") (pintype "bidirectional"))
      (node (ref "IC8") (pin "10") (pinfunction "P5_10") (pintype "bidirectional"))
    )
    (net (code "46") (name "PCF3_D6") (class "Default")
      (node (ref "CON3") (pin "2") (pinfunction "P$2_2") (pintype "bidirectional"))
      (node (ref "IC8") (pin "11") (pinfunction "P6_11") (pintype "bidirectional"))
    )
    (net (code "47") (name "PCF3_D7") (class "Default")
      (node (ref "CON3") (pin "1") (pinfunction "P$1_1") (pintype "bidirectional"))
      (node (ref "IC8") (pin "12") (pinfunction "P7_12") (pintype "bidirectional"))
    )
    (net (code "48") (name "RESET") (class "Default")
      (node (ref "D2") (pin "A") (pinfunction "A_A") (pintype "passive"))
      (node (ref "IC3") (pin "29") (pinfunction "PC6(/RESET)_29") (pintype "bidirectional"))
      (node (ref "JP3") (pin "5") (pinfunction "5_5") (pintype "passive"))
      (node (ref "R7") (pin "1") (pinfunction "1_1") (pintype "passive"))
      (node (ref "S1") (pin "1") (pinfunction "1_1") (pintype "passive"))
      (node (ref "S1") (pin "2") (pinfunction "2_2") (pintype "passive"))
    )
    (net (code "49") (name "RS485_A") (class "Default")
      (node (ref "CON1") (pin "2") (pinfunction "P$2_2") (pintype "bidirectional"))
      (node (ref "CON1") (pin "4") (pinfunction "P$4_4") (pintype "bidirectional"))
      (node (ref "CON1") (pin "6") (pinfunction "P$6_6") (pintype "bidirectional"))
      (node (ref "CON1") (pin "8") (pinfunction "P$8_8") (pintype "bidirectional"))
      (node (ref "IC2") (pin "6") (pinfunction "A_6") (pintype "passive"))
      (node (ref "JP5") (pin "3") (pinfunction "3_3") (pintype "passive"))
      (node (ref "R8") (pin "2") (pinfunction "2_2") (pintype "passive"))
      (node (ref "R9") (pin "2") (pinfunction "2_2") (pintype "passive"))
    )
    (net (code "50") (name "RS485_B") (class "Default")
      (node (ref "CON1") (pin "1") (pinfunction "P$1_1") (pintype "bidirectional"))
      (node (ref "CON1") (pin "3") (pinfunction "P$3_3") (pintype "bidirectional"))
      (node (ref "CON1") (pin "5") (pinfunction "P$5_5") (pintype "bidirectional"))
      (node (ref "CON1") (pin "7") (pinfunction "P$7_7") (pintype "bidirectional"))
      (node (ref "IC2") (pin "7") (pinfunction "B_7") (pintype "passive"))
      (node (ref "JP5") (pin "4") (pinfunction "4_4") (pintype "passive"))
      (node (ref "R10") (pin "1") (pinfunction "1_1") (pintype "passive"))
      (node (ref "R9") (pin "1") (pinfunction "1_1") (pintype "passive"))
    )
    (net (code "51") (name "RS485_DE") (class "Default")
      (node (ref "IC2") (pin "3") (pinfunction "DE_3") (pintype "input"))
      (node (ref "IC3") (pin "13") (pinfunction "PB1(OC1A)_13") (pintype "bidirectional"))
      (node (ref "R3") (pin "1") (pinfunction "1_1") (pintype "passive"))
    )
    (net (code "52") (name "RS485_RE") (class "Default")
      (node (ref "IC2") (pin "2") (pinfunction "RE/_2") (pintype "input"))
      (node (ref "IC3") (pin "10") (pinfunction "PD6(AIN0)_10") (pintype "bidirectional"))
      (node (ref "R2") (pin "1") (pinfunction "1_1") (pintype "passive"))
    )
    (net (code "53") (name "RXD") (class "Default")
      (node (ref "IC3") (pin "30") (pinfunction "PD0(RXD)_30") (pintype "bidirectional"))
      (node (ref "U1") (pin "5") (pinfunction "RXD_5") (pintype "input"))
    )
    (net (code "54") (name "SCK") (class "Default")
      (node (ref "IC3") (pin "17") (pinfunction "PB5(SCK)_17") (pintype "bidirectional"))
      (node (ref "JP3") (pin "3") (pinfunction "3_3") (pintype "passive"))
      (node (ref "P1") (pin "5") (pinfunction "CLK_5") (pintype "bidirectional"))
    )
    (net (code "55") (name "SCL") (class "Default")
      (node (ref "IC3") (pin "28") (pinfunction "PC5(ADC5/SCL)_28") (pintype "bidirectional"))
      (node (ref "IC6") (pin "14") (pinfunction "SCL_14") (pintype "input"))
      (node (ref "IC7") (pin "14") (pinfunction "SCL_14") (pintype "input"))
      (node (ref "IC8") (pin "14") (pinfunction "SCL_14") (pintype "input"))
      (node (ref "JP2") (pin "4") (pinfunction "4_4") (pintype "passive"))
      (node (ref "JP5") (pin "5") (pinfunction "5_5") (pintype "passive"))
      (node (ref "LED3") (pin "C") (pinfunction "C_C") (pintype "passive"))
    )
    (net (code "56") (name "SDA") (class "Default")
      (node (ref "IC3") (pin "27") (pinfunction "PC4(ADC4/SDA)_27") (pintype "bidirectional"))
      (node (ref "IC6") (pin "15") (pinfunction "SDA_15") (pintype "bidirectional"))
      (node (ref "IC7") (pin "15") (pinfunction "SDA_15") (pintype "bidirectional"))
      (node (ref "IC8") (pin "15") (pinfunction "SDA_15") (pintype "bidirectional"))
      (node (ref "JP2") (pin "3") (pinfunction "3_3") (pintype "passive"))
      (node (ref "JP5") (pin "6") (pinfunction "6_6") (pintype "passive"))
      (node (ref "R5") (pin "2") (pinfunction "2_2") (pintype "passive"))
    )
    (net (code "57") (name "SRXD") (class "Default")
      (node (ref "IC3") (pin "32") (pinfunction "PD2(INT0)_32") (pintype "bidirectional"))
      (node (ref "JP1") (pin "2") (pinfunction "2_2") (pintype "passive"))
    )
    (net (code "58") (name "SRXD_ESP") (class "Default")
      (node (ref "IC5") (pin "16") (pinfunction "TX_16") (pintype "bidirectional"))
      (node (ref "JP1") (pin "1") (pinfunction "1_1") (pintype "passive"))
    )
    (net (code "59") (name "SRXD_MAX") (class "Default")
      (node (ref "IC2") (pin "1") (pinfunction "RO_1") (pintype "output"))
      (node (ref "JP1") (pin "3") (pinfunction "3_3") (pintype "passive"))
      (node (ref "LED1") (pin "C") (pinfunction "C_C") (pintype "passive"))
    )
    (net (code "60") (name "STXD") (class "Default")
      (node (ref "IC3") (pin "1") (pinfunction "PD3(INT1)_1") (pintype "bidirectional"))
      (node (ref "JP1") (pin "5") (pinfunction "5_5") (pintype "passive"))
    )
    (net (code "61") (name "STXD_ESP") (class "Default")
      (node (ref "IC5") (pin "15") (pinfunction "RX_15") (pintype "bidirectional"))
      (node (ref "JP1") (pin "4") (pinfunction "4_4") (pintype "passive"))
    )
    (net (code "62") (name "STXD_MAX") (class "Default")
      (node (ref "IC2") (pin "4") (pinfunction "DI_4") (pintype "input"))
      (node (ref "JP1") (pin "6") (pinfunction "6_6") (pintype "passive"))
      (node (ref "LED2") (pin "C") (pinfunction "C_C") (pintype "passive"))
    )
    (net (code "63") (name "TXD") (class "Default")
      (node (ref "IC3") (pin "31") (pinfunction "PD1(TXD)_31") (pintype "bidirectional"))
      (node (ref "U1") (pin "1") (pinfunction "TXD_1") (pintype "output"))
    )
    (net (code "64") (name "USBDM") (class "Default")
      (node (ref "U1") (pin "16") (pinfunction "USBDM_16") (pintype "bidirectional"))
      (node (ref "X1") (pin "2") (pinfunction "2_2") (pintype "passive"))
    )
    (net (code "65") (name "USBDP") (class "Default")
      (node (ref "U1") (pin "15") (pinfunction "USBDP_15") (pintype "bidirectional"))
      (node (ref "X1") (pin "3") (pinfunction "3_3") (pintype "passive"))
    )
    (net (code "66") (name "VCC") (class "Default")
      (node (ref "C1") (pin "+") (pinfunction "+_+") (pintype "passive"))
      (node (ref "C14") (pin "1") (pinfunction "1_1") (pintype "passive"))
      (node (ref "C2") (pin "+") (pinfunction "+_+") (pintype "passive"))
      (node (ref "C3") (pin "2") (pinfunction "2_2") (pintype "passive"))
      (node (ref "C4") (pin "2") (pinfunction "2_2") (pintype "passive"))
      (node (ref "C7") (pin "+") (pinfunction "+_+") (pintype "passive"))
      (node (ref "C8") (pin "1") (pinfunction "1_1") (pintype "passive"))
      (node (ref "D1") (pin "C") (pinfunction "C_C") (pintype "passive"))
      (node (ref "IC1") (pin "1") (pinfunction "VI_1") (pintype "input"))
      (node (ref "IC4") (pin "1") (pinfunction "VI_1") (pintype "input"))
    )
    (net (code "67") (name "unconnected-(IC3-ADC6-Pad19)") (class "Default")
      (node (ref "IC3") (pin "19") (pinfunction "ADC6_19") (pintype "bidirectional"))
    )
    (net (code "68") (name "unconnected-(IC3-ADC7-Pad22)") (class "Default")
      (node (ref "IC3") (pin "22") (pinfunction "ADC7_22") (pintype "bidirectional"))
    )
    (net (code "69") (name "unconnected-(IC3-PB0(ICP)-Pad12)") (class "Default")
      (node (ref "IC3") (pin "12") (pinfunction "PB0(ICP)_12") (pintype "bidirectional"))
    )
    (net (code "70") (name "unconnected-(IC3-PC0(ADC0)-Pad23)") (class "Default")
      (node (ref "IC3") (pin "23") (pinfunction "PC0(ADC0)_23") (pintype "bidirectional"))
    )
    (net (code "71") (name "unconnected-(IC3-PC1(ADC1)-Pad24)") (class "Default")
      (node (ref "IC3") (pin "24") (pinfunction "PC1(ADC1)_24") (pintype "bidirectional"))
    )
    (net (code "72") (name "unconnected-(IC3-PC2(ADC2)-Pad25)") (class "Default")
      (node (ref "IC3") (pin "25") (pinfunction "PC2(ADC2)_25") (pintype "bidirectional"))
    )
    (net (code "73") (name "unconnected-(IC3-PC3(ADC3)-Pad26)") (class "Default")
      (node (ref "IC3") (pin "26") (pinfunction "PC3(ADC3)_26") (pintype "bidirectional"))
    )
    (net (code "74") (name "unconnected-(IC3-PD5(T1)-Pad9)") (class "Default")
      (node (ref "IC3") (pin "9") (pinfunction "PD5(T1)_9") (pintype "bidirectional"))
    )
    (net (code "75") (name "unconnected-(IC3-PD7(AIN1)-Pad11)") (class "Default")
      (node (ref "IC3") (pin "11") (pinfunction "PD7(AIN1)_11") (pintype "bidirectional"))
    )
    (net (code "76") (name "unconnected-(IC5-ADC-Pad2)") (class "Default")
      (node (ref "IC5") (pin "2") (pinfunction "ADC_2") (pintype "bidirectional"))
    )
    (net (code "77") (name "unconnected-(IC5-GPIO0-Pad12)") (class "Default")
      (node (ref "IC5") (pin "12") (pinfunction "GPIO0_12") (pintype "bidirectional"))
    )
    (net (code "78") (name "unconnected-(IC5-GPIO4-Pad14)") (class "Default")
      (node (ref "IC5") (pin "14") (pinfunction "GPIO4_14") (pintype "bidirectional"))
    )
    (net (code "79") (name "unconnected-(IC5-GPIO5-Pad13)") (class "Default")
      (node (ref "IC5") (pin "13") (pinfunction "GPIO5_13") (pintype "bidirectional"))
    )
    (net (code "80") (name "unconnected-(IC5-GPIO12-Pad6)") (class "Default")
      (node (ref "IC5") (pin "6") (pinfunction "GPIO12_6") (pintype "bidirectional"))
    )
    (net (code "81") (name "unconnected-(IC5-GPIO13-Pad7)") (class "Default")
      (node (ref "IC5") (pin "7") (pinfunction "GPIO13_7") (pintype "bidirectional"))
    )
    (net (code "82") (name "unconnected-(IC5-GPIO14-Pad5)") (class "Default")
      (node (ref "IC5") (pin "5") (pinfunction "GPIO14_5") (pintype "bidirectional"))
    )
    (net (code "83") (name "unconnected-(IC5-GPIO16-Pad4)") (class "Default")
      (node (ref "IC5") (pin "4") (pinfunction "GPIO16_4") (pintype "bidirectional"))
    )
    (net (code "84") (name "unconnected-(IC6-~{INT}-Pad13)") (class "Default")
      (node (ref "IC6") (pin "13") (pinfunction "~{INT}_13") (pintype "output"))
    )
    (net (code "85") (name "unconnected-(IC7-~{INT}-Pad13)") (class "Default")
      (node (ref "IC7") (pin "13") (pinfunction "~{INT}_13") (pintype "output"))
    )
    (net (code "86") (name "unconnected-(IC8-~{INT}-Pad13)") (class "Default")
      (node (ref "IC8") (pin "13") (pinfunction "~{INT}_13") (pintype "output"))
    )
    (net (code "87") (name "unconnected-(IC10-PadNO)") (class "Default")
      (node (ref "IC10") (pin "NO") (pinfunction "NO_NO") (pintype "bidirectional"))
    )
    (net (code "88") (name "unconnected-(P1-DAT1-Pad8)") (class "Default")
      (node (ref "P1") (pin "8") (pinfunction "DAT1_8") (pintype "bidirectional"))
    )
    (net (code "89") (name "unconnected-(U1-CBUS2-Pad13)") (class "Default")
      (node (ref "U1") (pin "13") (pinfunction "CBUS2_13") (pintype "bidirectional"))
    )
    (net (code "90") (name "unconnected-(U1-CBUS3-Pad14)") (class "Default")
      (node (ref "U1") (pin "14") (pinfunction "CBUS3_14") (pintype "bidirectional"))
    )
    (net (code "91") (name "unconnected-(U1-CBUS4-Pad12)") (class "Default")
      (node (ref "U1") (pin "12") (pinfunction "CBUS4_12") (pintype "bidirectional"))
    )
    (net (code "92") (name "unconnected-(U1-CTS#-Pad11)") (class "Default")
      (node (ref "U1") (pin "11") (pinfunction "CTS#_11") (pintype "input"))
    )
    (net (code "93") (name "unconnected-(U1-DCD#-Pad10)") (class "Default")
      (node (ref "U1") (pin "10") (pinfunction "DCD#_10") (pintype "input"))
    )
    (net (code "94") (name "unconnected-(U1-DSR#-Pad9)") (class "Default")
      (node (ref "U1") (pin "9") (pinfunction "DSR#_9") (pintype "input"))
    )
    (net (code "95") (name "unconnected-(U1-DTR#-Pad2)") (class "Default")
      (node (ref "U1") (pin "2") (pinfunction "DTR#_2") (pintype "output"))
    )
    (net (code "96") (name "unconnected-(U1-OSCI-Pad27)") (class "Default")
      (node (ref "U1") (pin "27") (pinfunction "OSCI_27") (pintype "input"))
    )
    (net (code "97") (name "unconnected-(U1-OSCO-Pad28)") (class "Default")
      (node (ref "U1") (pin "28") (pinfunction "OSCO_28") (pintype "output"))
    )
    (net (code "98") (name "unconnected-(U1-RESET#-Pad19)") (class "Default")
      (node (ref "U1") (pin "19") (pinfunction "RESET#_19") (pintype "input"))
    )
    (net (code "99") (name "unconnected-(U1-RI#-Pad6)") (class "Default")
      (node (ref "U1") (pin "6") (pinfunction "RI#_6") (pintype "input"))
    )
    (net (code "100") (name "unconnected-(U1-RTS#-Pad3)") (class "Default")
      (node (ref "U1") (pin "3") (pinfunction "RTS#_3") (pintype "output"))
    )
    (net (code "101") (name "unconnected-(X1-Pad1)") (class "Default")
      (node (ref "X1") (pin "1") (pinfunction "1_1") (pintype "passive"))
    )
  )
)
